# mcu_power.net
KiCad netlist of a schematic drawn in Altium Designer
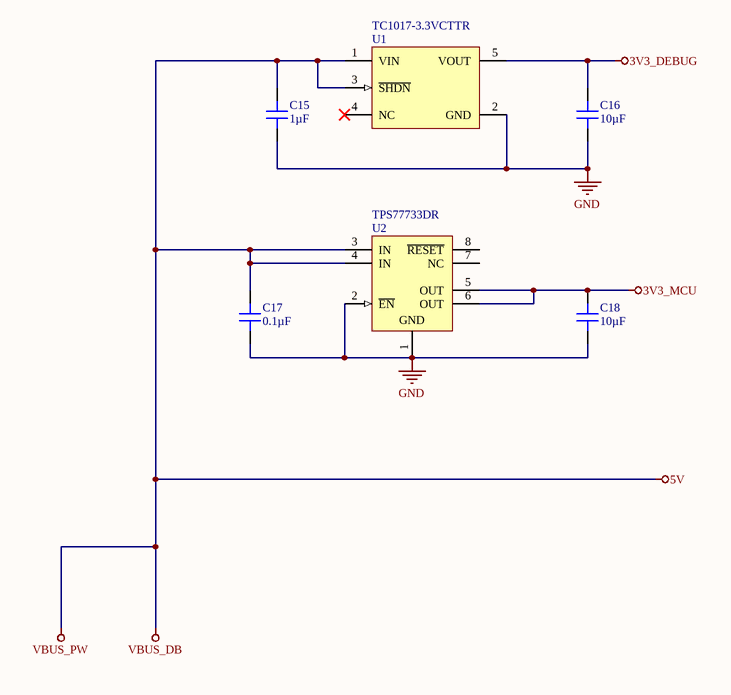
[diagram p0: mcu_power.SchDoc]

(export (version "E")
  (design (tool "Eeschema 10.0.6"))
  (components
    (comp (ref "C15")
      (value "1µF")
      (footprint "CAP 0603_1608")
      (description "CAP CER 0603 1UF 16V X7R 20%")
      (fields (field (name "PART NUMBER") "C0603X105M4RACAUTO") (field (name "MANUFACTURER") "KEMET"))
      (libsource (lib "Celestial Altium Library - altium_library (2)") (part "Capacitor"))
    )
    (comp (ref "C16")
      (value "10µF")
      (footprint "CAP 0603_1608")
      (description "CAP CER 10UF 16V X5R 0603")
      (fields
        (field (name "PART NUMBER") "GRT188R61C106KE13D")
        (field (name "MANUFACTURER") "Murata Electronics")
      )
      (libsource (lib "Celestial Altium Library - altium_library (2)") (part "Capacitor"))
    )
    (comp (ref "C17")
      (value "0.1µF")
      (footprint "CAP 0603_1608")
      (description "CAP CER 0.1UF 16V X7R 0603")
      (fields (field (name "PART NUMBER") "CS0603KRX7R7BB104") (field (name "MANUFACTURER") "Yageo"))
      (libsource (lib "Celestial Altium Library - altium_library (2)") (part "Capacitor"))
    )
    (comp (ref "C18")
      (value "10µF")
      (footprint "CAP 0603_1608")
      (description "CAP CER 10UF 16V X5R 0603")
      (fields
        (field (name "PART NUMBER") "GRT188R61C106KE13D")
        (field (name "MANUFACTURER") "Murata Electronics")
      )
      (libsource (lib "Celestial Altium Library - altium_library (2)") (part "Capacitor"))
    )
    (comp (ref "U1")
      (value "TC1017-3.3VCTTR")
      (footprint "SOT-23-CT5_L")
      (description "150 mA, Tiny CMOS LDO with Shutdown, 5-Pin SOT-23, Extended Temperature, Tape and Reel")
      (libsource (lib "Altium Content Vault") (part "PM-LINEREG-TC1017-IL5A"))
    )
    (comp (ref "U2")
      (value "TPS77733DR")
      (footprint "D0008A_N")
      (fields (field (name "MANUFACTURER") "Texas Instruments"))
      (libsource (lib "Altium Content Vault") (part "TI-TPS7XXXXD8"))
    )
  )
  (nets
    (net (code "1") (name "3V3_DEBUG") (class "Default")
      (node (ref "C16") (pin "2") (pinfunction "2_2") (pintype "passive"))
      (node (ref "U1") (pin "5") (pinfunction "VOUT_5") (pintype "power_in"))
    )
    (net (code "2") (name "3V3_MCU") (class "Default")
      (node (ref "C18") (pin "2") (pinfunction "2_2") (pintype "passive"))
      (node (ref "U2") (pin "5") (pinfunction "OUT_5") (pintype "power_in"))
      (node (ref "U2") (pin "6") (pinfunction "OUT_6") (pintype "power_in"))
    )
    (net (code "3") (name "5V") (class "Default")
      (node (ref "C15") (pin "2") (pinfunction "2_2") (pintype "passive"))
      (node (ref "C17") (pin "2") (pinfunction "2_2") (pintype "passive"))
      (node (ref "U1") (pin "1") (pinfunction "VIN_1") (pintype "power_in"))
      (node (ref "U1") (pin "3") (pinfunction "~{SHDN}_3") (pintype "input"))
      (node (ref "U2") (pin "3") (pinfunction "IN_3") (pintype "power_in"))
      (node (ref "U2") (pin "4") (pinfunction "IN_4") (pintype "power_in"))
    )
    (net (code "4") (name "GND") (class "Default")
      (node (ref "C15") (pin "1") (pinfunction "1_1") (pintype "passive"))
      (node (ref "C16") (pin "1") (pinfunction "1_1") (pintype "passive"))
      (node (ref "C17") (pin "1") (pinfunction "1_1") (pintype "passive"))
      (node (ref "C18") (pin "1") (pinfunction "1_1") (pintype "passive"))
      (node (ref "U1") (pin "2") (pinfunction "GND_2") (pintype "power_in"))
      (node (ref "U2") (pin "1") (pinfunction "GND_1") (pintype "power_in"))
      (node (ref "U2") (pin "2") (pinfunction "~{EN}_2") (pintype "input"))
    )
    (net (code "5") (name "unconnected-(U1-NC-Pad4)") (class "Default")
      (node (ref "U1") (pin "4") (pinfunction "NC_4") (pintype "passive+no_connect"))
    )
    (net (code "6") (name "unconnected-(U2-NC-Pad7)") (class "Default")
      (node (ref "U2") (pin "7") (pinfunction "NC_7") (pintype "passive"))
    )
    (net (code "7") (name "unconnected-(U2-~{RESET}-Pad8)") (class "Default")
      (node (ref "U2") (pin "8") (pinfunction "~{RESET}_8") (pintype "tri_state"))
    )
  )
)
